# sGPSDO_MCU_1V1.net
KiCad netlist of a schematic drawn in EAGLE
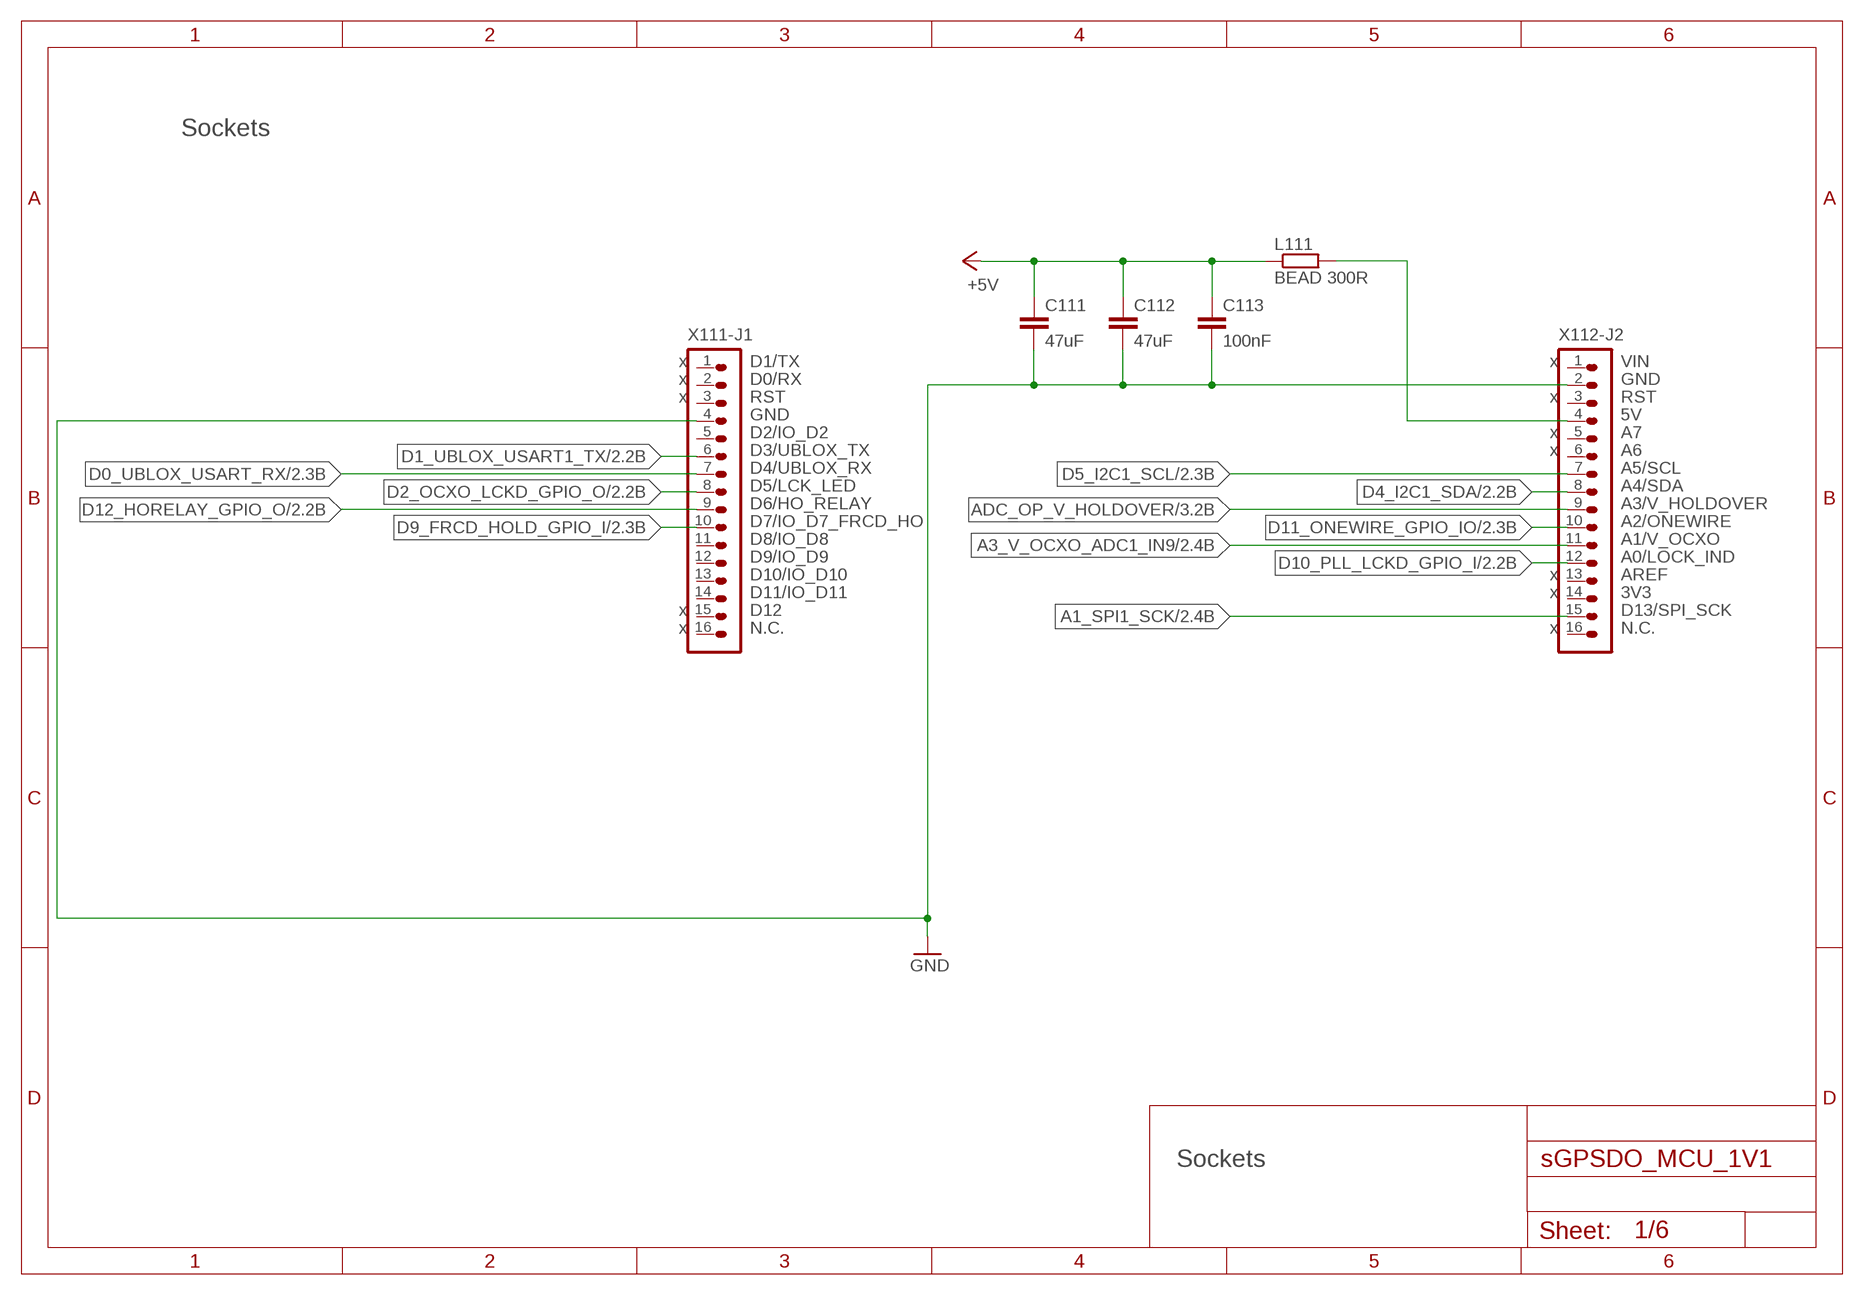
[diagram p0: schematic, sheet 1]
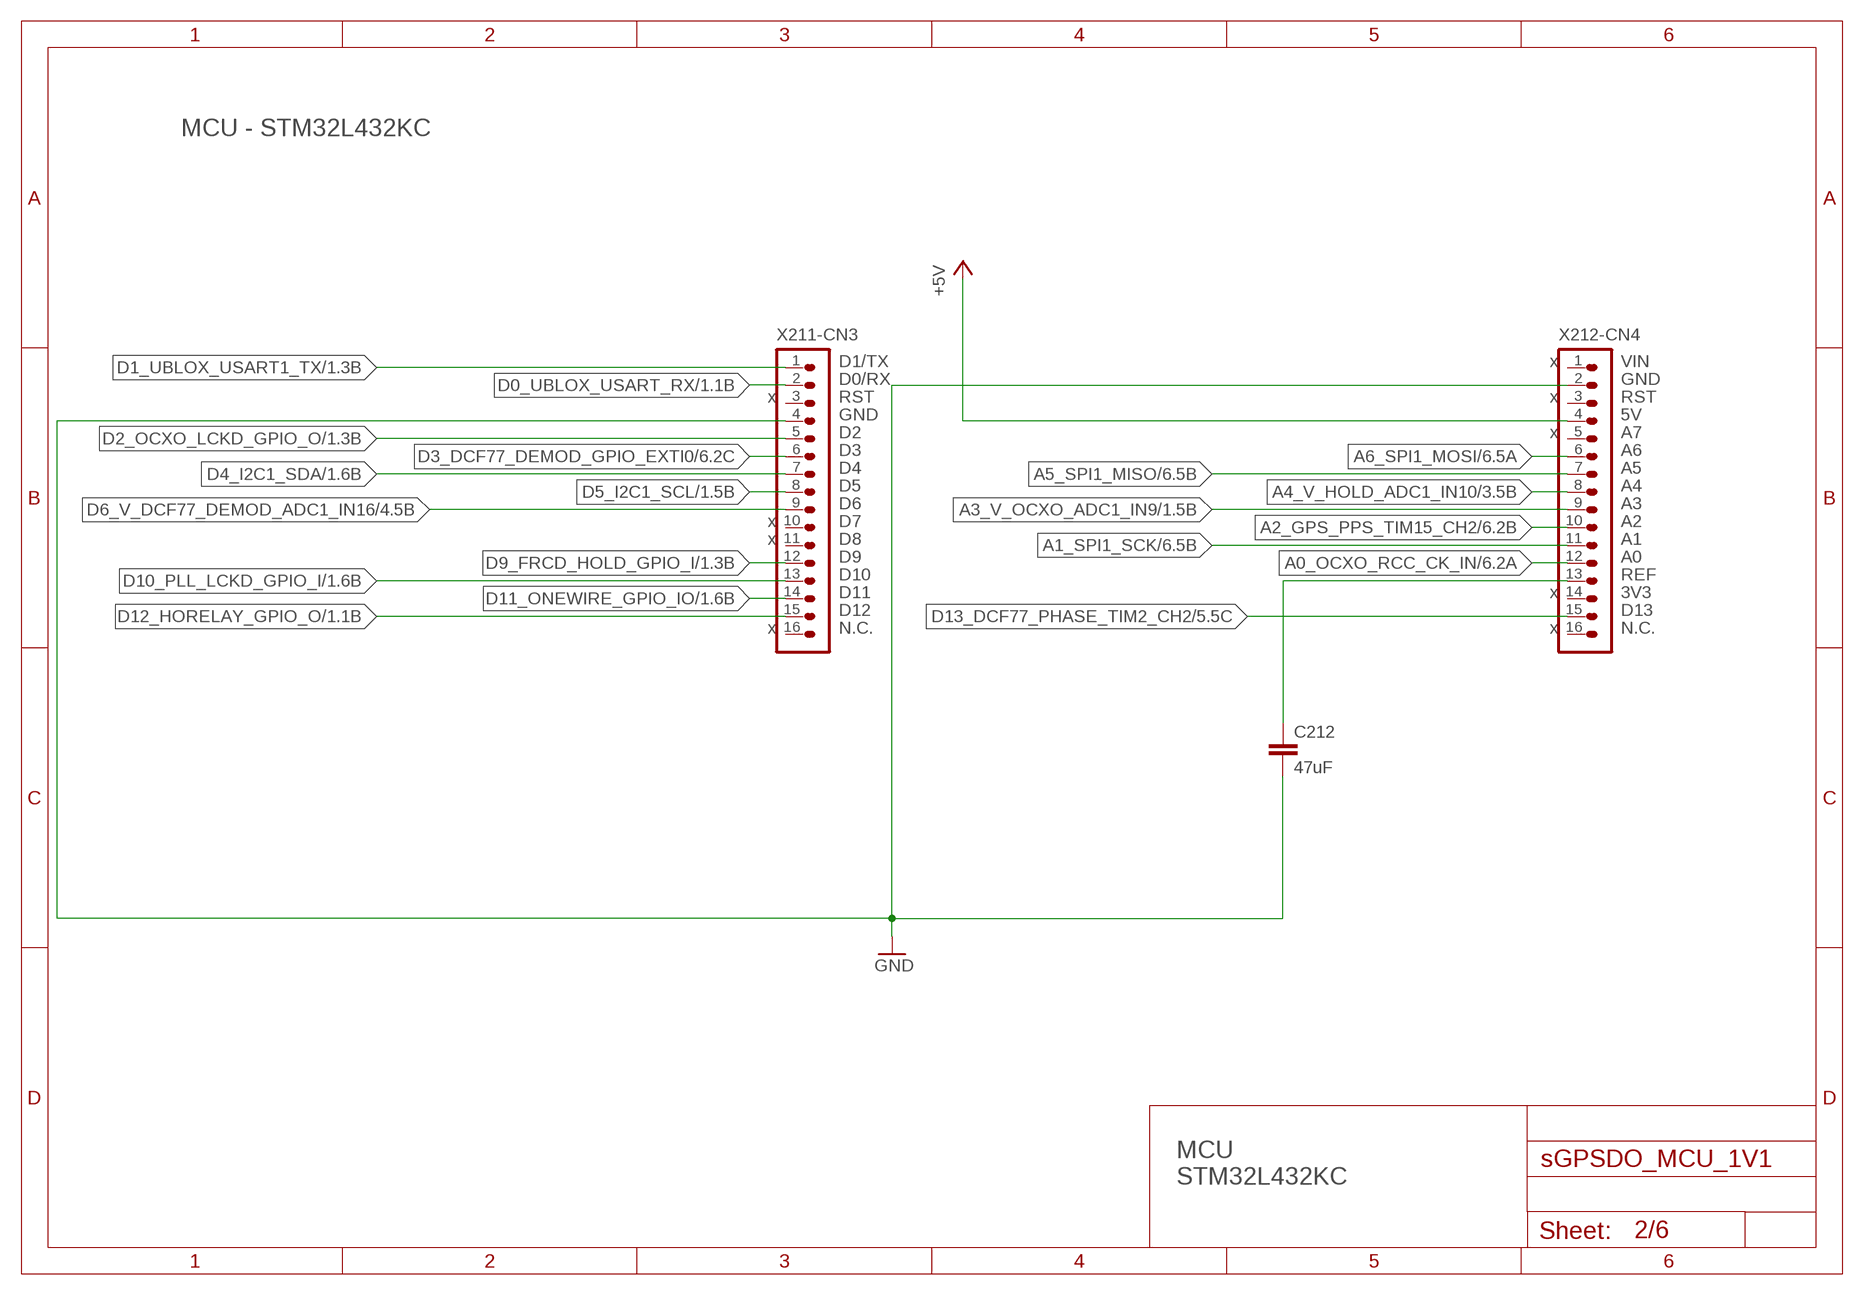
[diagram p1: schematic, sheet 2]
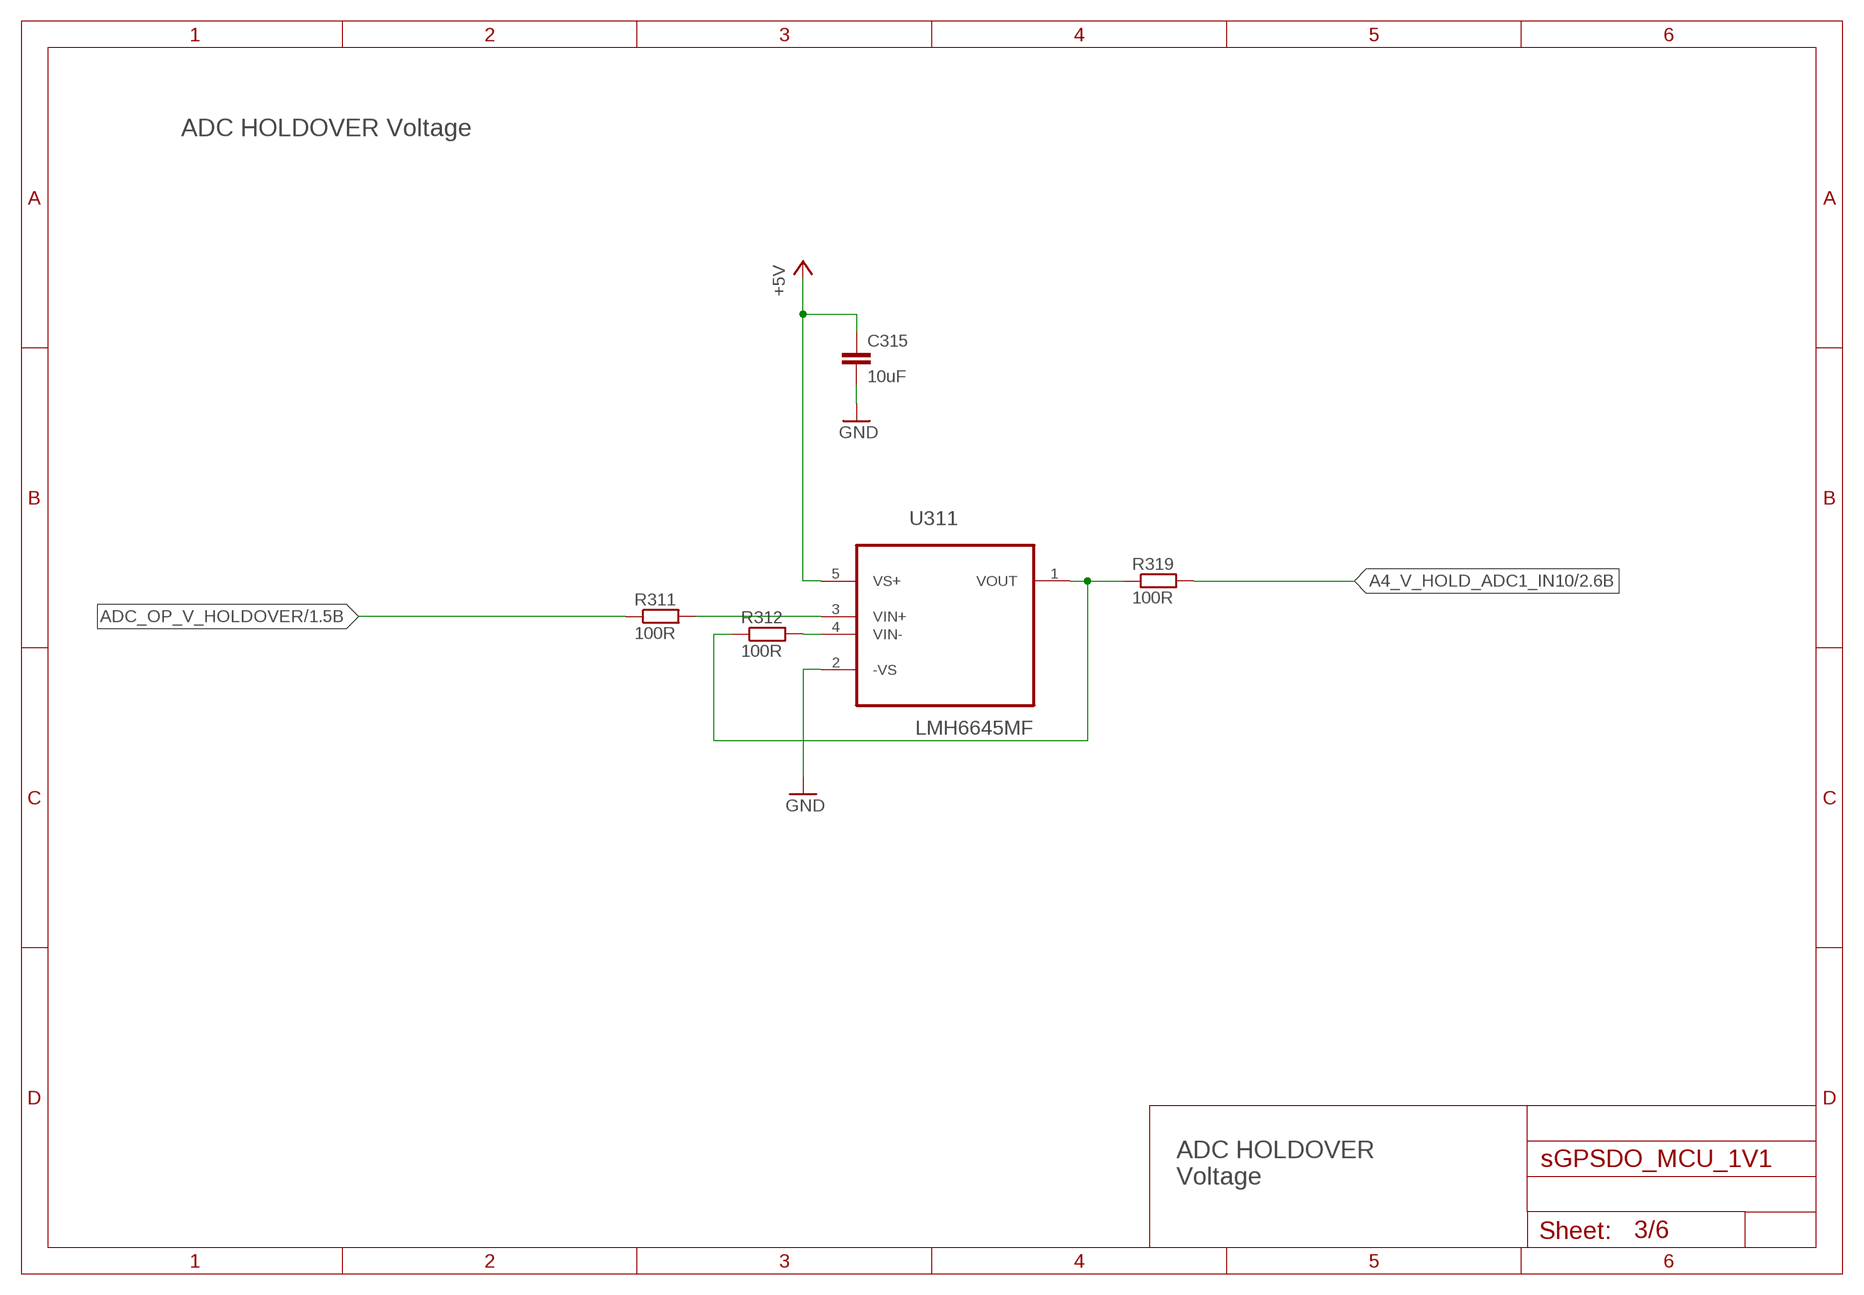
[diagram p2: schematic, sheet 3]
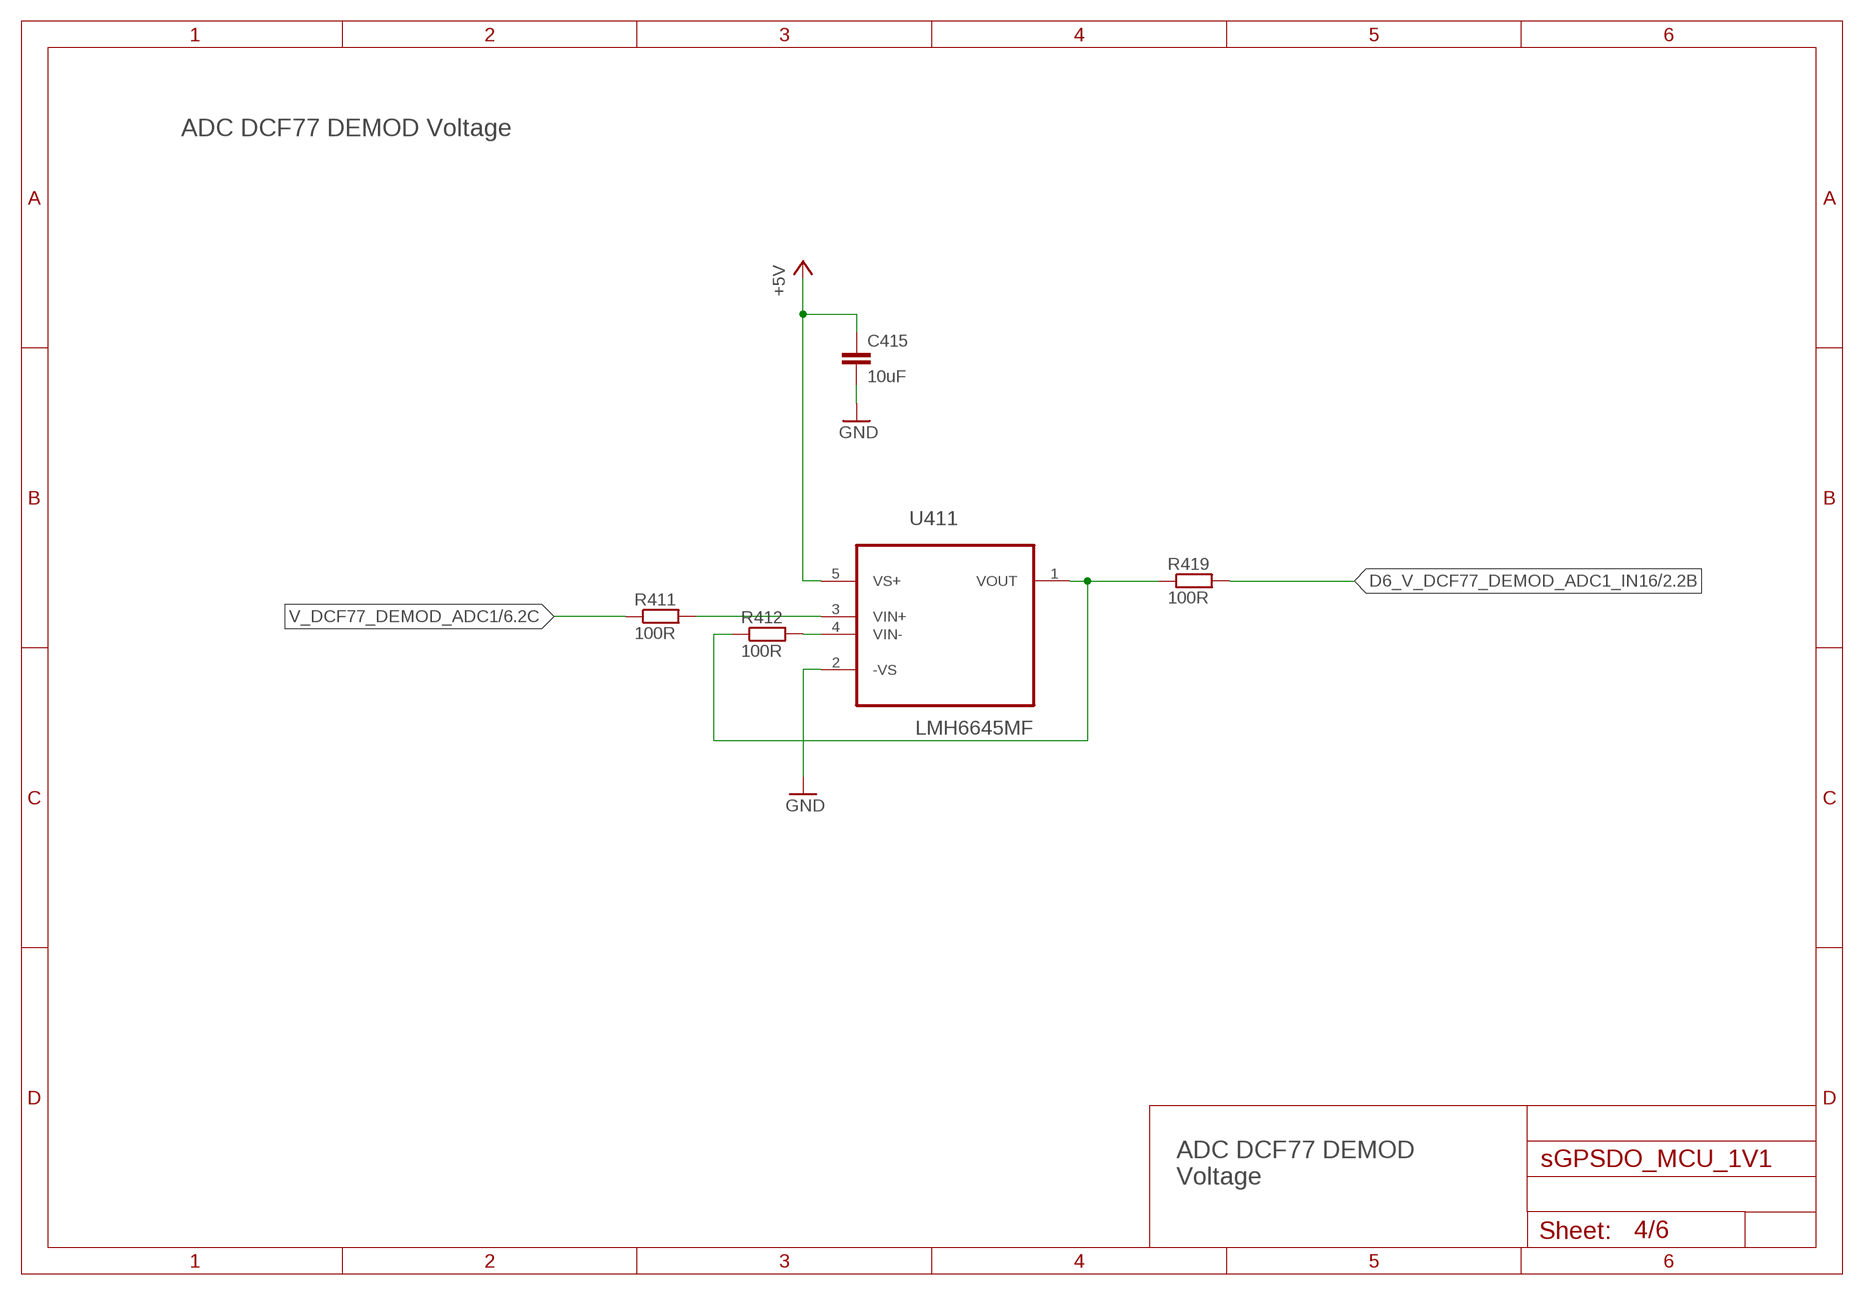
[diagram p3: schematic, sheet 4]
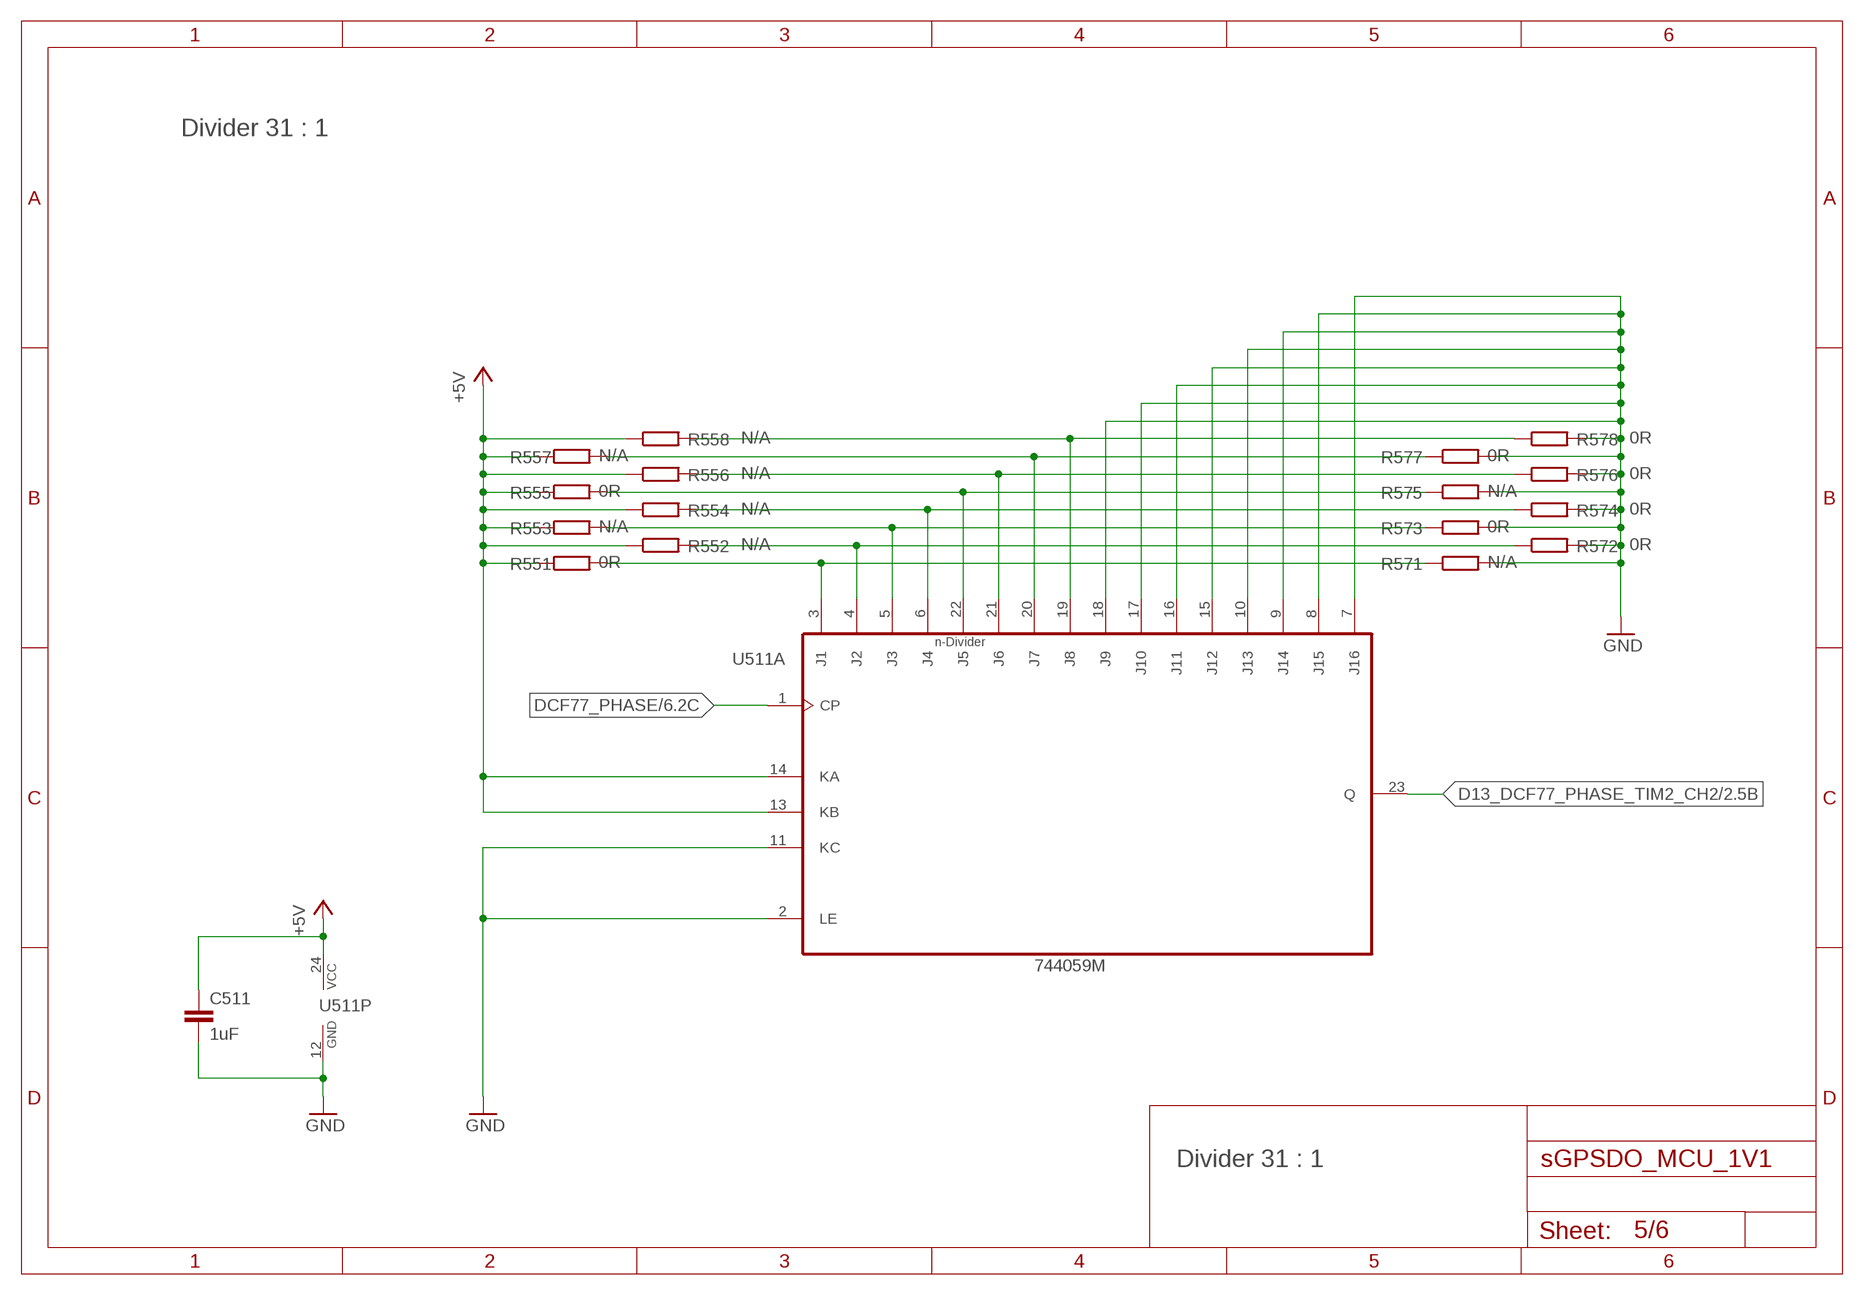
[diagram p4: schematic, sheet 5]
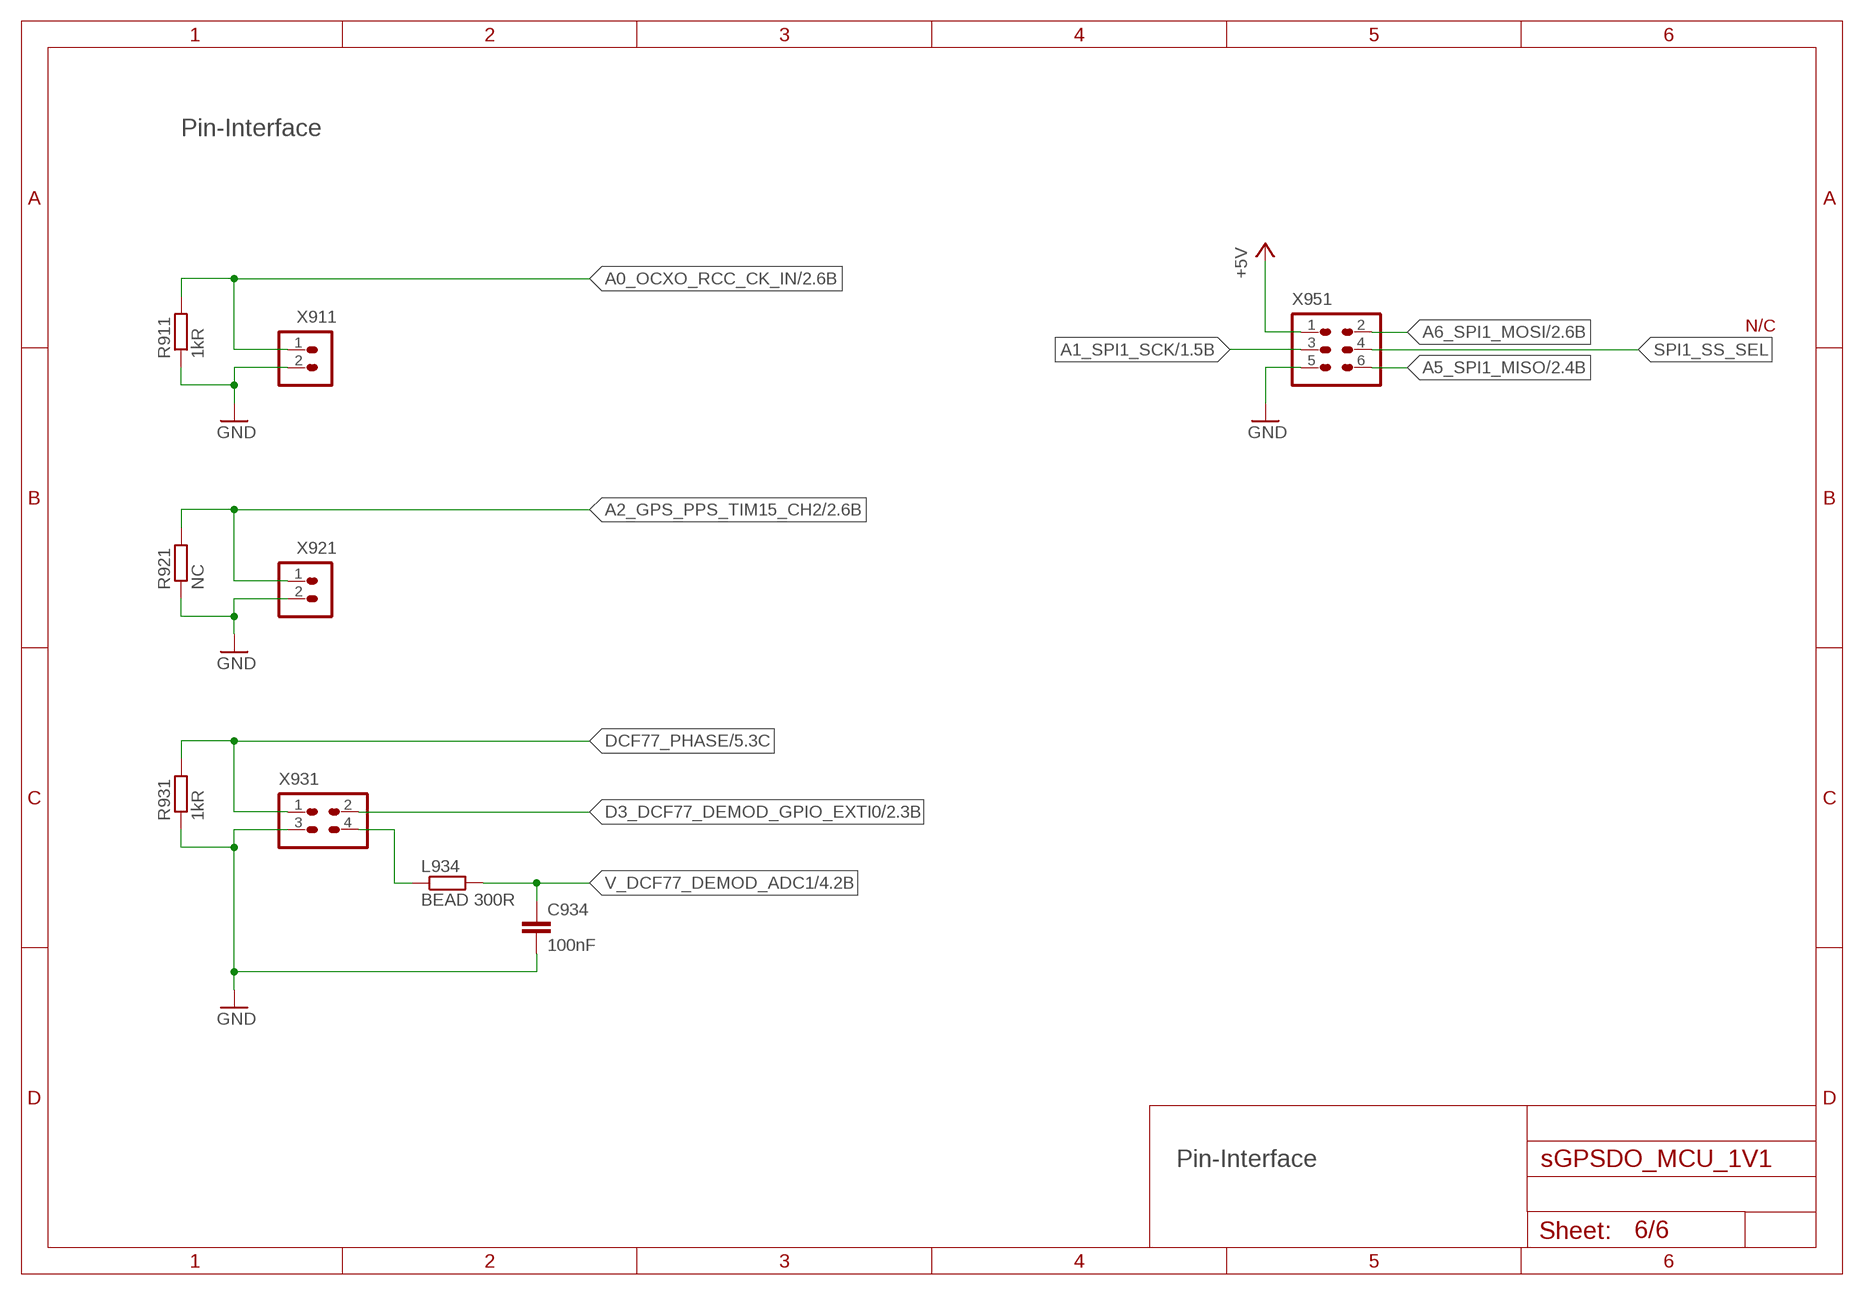
[diagram p5: schematic, sheet 6]

(export (version "E")
  (design (tool "Eeschema 10.0.6"))
  (components
    (comp (ref "C511")
      (value "1uF")
      (footprint "eagle-import:C0805")
      (libsource (lib "eagle-import") (part "C-EUC0805"))
    )
    (comp (ref "R551")
      (value "0R")
      (footprint "eagle-import:R0402")
      (libsource (lib "eagle-import") (part "R-EU_R0402"))
    )
    (comp (ref "R552")
      (value "N/A")
      (footprint "eagle-import:R0402")
      (libsource (lib "eagle-import") (part "R-EU_R0402"))
    )
    (comp (ref "R553")
      (value "N/A")
      (footprint "eagle-import:R0402")
      (libsource (lib "eagle-import") (part "R-EU_R0402"))
    )
    (comp (ref "R554")
      (value "N/A")
      (footprint "eagle-import:R0402")
      (libsource (lib "eagle-import") (part "R-EU_R0402"))
    )
    (comp (ref "R555")
      (value "0R")
      (footprint "eagle-import:R0402")
      (libsource (lib "eagle-import") (part "R-EU_R0402"))
    )
    (comp (ref "R556")
      (value "N/A")
      (footprint "eagle-import:R0402")
      (libsource (lib "eagle-import") (part "R-EU_R0402"))
    )
    (comp (ref "R557")
      (value "N/A")
      (footprint "eagle-import:R0402")
      (libsource (lib "eagle-import") (part "R-EU_R0402"))
    )
    (comp (ref "R558")
      (value "N/A")
      (footprint "eagle-import:R0402")
      (libsource (lib "eagle-import") (part "R-EU_R0402"))
    )
    (comp (ref "R571")
      (value "N/A")
      (footprint "eagle-import:R0402")
      (libsource (lib "eagle-import") (part "R-EU_R0402"))
    )
    (comp (ref "R572")
      (value "0R")
      (footprint "eagle-import:R0402")
      (libsource (lib "eagle-import") (part "R-EU_R0402"))
    )
    (comp (ref "R573")
      (value "0R")
      (footprint "eagle-import:R0402")
      (libsource (lib "eagle-import") (part "R-EU_R0402"))
    )
    (comp (ref "R574")
      (value "0R")
      (footprint "eagle-import:R0402")
      (libsource (lib "eagle-import") (part "R-EU_R0402"))
    )
    (comp (ref "R575")
      (value "N/A")
      (footprint "eagle-import:R0402")
      (libsource (lib "eagle-import") (part "R-EU_R0402"))
    )
    (comp (ref "R576")
      (value "0R")
      (footprint "eagle-import:R0402")
      (libsource (lib "eagle-import") (part "R-EU_R0402"))
    )
    (comp (ref "R577")
      (value "0R")
      (footprint "eagle-import:R0402")
      (libsource (lib "eagle-import") (part "R-EU_R0402"))
    )
    (comp (ref "R578")
      (value "0R")
      (footprint "eagle-import:R0402")
      (libsource (lib "eagle-import") (part "R-EU_R0402"))
    )
    (comp (ref "U511")
      (value "744059M")
      (footprint "eagle-import:SOIC24")
      (libsource (lib "eagle-import") (part "744059M"))
    )
    (comp (ref "C111")
      (value "47uF")
      (footprint "eagle-import:C0805")
      (libsource (lib "eagle-import") (part "C-EUC0805"))
    )
    (comp (ref "C112")
      (value "47uF")
      (footprint "eagle-import:C0805")
      (libsource (lib "eagle-import") (part "C-EUC0805"))
    )
    (comp (ref "C113")
      (value "100nF")
      (footprint "eagle-import:C0805")
      (libsource (lib "eagle-import") (part "C-EUC0805"))
    )
    (comp (ref "L111")
      (value "BEAD 300R")
      (footprint "eagle-import:R1206")
      (libsource (lib "eagle-import") (part "R-EU_R1206"))
    )
    (comp (ref "X111-J1")
      (value "HEADER-1X16")
      (footprint "eagle-import:1X16")
      (libsource (lib "eagle-import") (part "HEADER-1X16"))
    )
    (comp (ref "X112-J2")
      (value "HEADER-1X16")
      (footprint "eagle-import:1X16")
      (libsource (lib "eagle-import") (part "HEADER-1X16"))
    )
    (comp (ref "C415")
      (value "10uF")
      (footprint "eagle-import:C0805")
      (libsource (lib "eagle-import") (part "C-EUC0805"))
    )
    (comp (ref "R411")
      (value "100R")
      (footprint "eagle-import:R0805")
      (libsource (lib "eagle-import") (part "R-EU_R0805"))
    )
    (comp (ref "R412")
      (value "100R")
      (footprint "eagle-import:R0805")
      (libsource (lib "eagle-import") (part "R-EU_R0805"))
    )
    (comp (ref "R419")
      (value "100R")
      (footprint "eagle-import:R0805")
      (libsource (lib "eagle-import") (part "R-EU_R0805"))
    )
    (comp (ref "U411")
      (value "LMH6645MF")
      (footprint "eagle-import:SOT-23-5")
      (libsource (lib "eagle-import") (part "LMH6645MF"))
    )
    (comp (ref "C212")
      (value "47uF")
      (footprint "eagle-import:C0805")
      (libsource (lib "eagle-import") (part "C-EUC0805"))
    )
    (comp (ref "X211-CN3")
      (value "HEADER-1X16")
      (footprint "eagle-import:1X16")
      (libsource (lib "eagle-import") (part "HEADER-1X16"))
    )
    (comp (ref "X212-CN4")
      (value "HEADER-1X16")
      (footprint "eagle-import:1X16")
      (libsource (lib "eagle-import") (part "HEADER-1X16"))
    )
    (comp (ref "C934")
      (value "100nF")
      (footprint "eagle-import:C0805")
      (libsource (lib "eagle-import") (part "C-EUC0805"))
    )
    (comp (ref "L934")
      (value "BEAD 300R")
      (footprint "eagle-import:R1206")
      (libsource (lib "eagle-import") (part "R-EU_R1206"))
    )
    (comp (ref "R911")
      (value "1kR")
      (footprint "eagle-import:R0805")
      (libsource (lib "eagle-import") (part "R-EU_R0805"))
    )
    (comp (ref "R921")
      (value "NC")
      (footprint "eagle-import:R0805")
      (libsource (lib "eagle-import") (part "R-EU_R0805"))
    )
    (comp (ref "R931")
      (value "1kR")
      (footprint "eagle-import:R0805")
      (libsource (lib "eagle-import") (part "R-EU_R0805"))
    )
    (comp (ref "X911")
      (value "HEADER-1X2")
      (footprint "eagle-import:1X02")
      (libsource (lib "eagle-import") (part "HEADER-1X2"))
    )
    (comp (ref "X921")
      (value "HEADER-1X2")
      (footprint "eagle-import:1X02")
      (libsource (lib "eagle-import") (part "HEADER-1X2"))
    )
    (comp (ref "X931")
      (value "HEADER-2X2")
      (footprint "eagle-import:2X02")
      (libsource (lib "eagle-import") (part "HEADER-2X2"))
    )
    (comp (ref "X951")
      (value "HEADER-2X3")
      (footprint "eagle-import:2X03")
      (libsource (lib "eagle-import") (part "HEADER-2X3"))
    )
    (comp (ref "C315")
      (value "10uF")
      (footprint "eagle-import:C0805")
      (libsource (lib "eagle-import") (part "C-EUC0805"))
    )
    (comp (ref "R311")
      (value "100R")
      (footprint "eagle-import:R0805")
      (libsource (lib "eagle-import") (part "R-EU_R0805"))
    )
    (comp (ref "R312")
      (value "100R")
      (footprint "eagle-import:R0805")
      (libsource (lib "eagle-import") (part "R-EU_R0805"))
    )
    (comp (ref "R319")
      (value "100R")
      (footprint "eagle-import:R0805")
      (libsource (lib "eagle-import") (part "R-EU_R0805"))
    )
    (comp (ref "U311")
      (value "LMH6645MF")
      (footprint "eagle-import:SOT-23-5")
      (libsource (lib "eagle-import") (part "LMH6645MF"))
    )
  )
  (nets
    (net (code "1") (name "+5V") (class "Default")
      (node (ref "C111") (pin "1") (pinfunction "1_1") (pintype "passive"))
      (node (ref "C112") (pin "1") (pinfunction "1_1") (pintype "passive"))
      (node (ref "C113") (pin "1") (pinfunction "1_1") (pintype "passive"))
      (node (ref "C315") (pin "1") (pinfunction "1_1") (pintype "passive"))
      (node (ref "C415") (pin "1") (pinfunction "1_1") (pintype "passive"))
      (node (ref "C511") (pin "1") (pinfunction "1_1") (pintype "passive"))
      (node (ref "L111") (pin "1") (pinfunction "1_1") (pintype "passive"))
      (node (ref "R551") (pin "1") (pinfunction "1_1") (pintype "passive"))
      (node (ref "R552") (pin "1") (pinfunction "1_1") (pintype "passive"))
      (node (ref "R553") (pin "1") (pinfunction "1_1") (pintype "passive"))
      (node (ref "R554") (pin "1") (pinfunction "1_1") (pintype "passive"))
      (node (ref "R555") (pin "1") (pinfunction "1_1") (pintype "passive"))
      (node (ref "R556") (pin "1") (pinfunction "1_1") (pintype "passive"))
      (node (ref "R557") (pin "1") (pinfunction "1_1") (pintype "passive"))
      (node (ref "R558") (pin "1") (pinfunction "1_1") (pintype "passive"))
      (node (ref "U311") (pin "5") (pinfunction "VS+_5") (pintype "power_in"))
      (node (ref "U411") (pin "5") (pinfunction "VS+_5") (pintype "power_in"))
      (node (ref "U511") (pin "13") (pinfunction "KB_13") (pintype "input"))
      (node (ref "U511") (pin "14") (pinfunction "KA_14") (pintype "input"))
      (node (ref "U511") (pin "24") (pinfunction "VCC_24") (pintype "power_in"))
      (node (ref "X212-CN4") (pin "4") (pinfunction "4_4") (pintype "passive"))
      (node (ref "X951") (pin "1") (pinfunction "1_1") (pintype "passive"))
    )
    (net (code "2") (name "A0_OCXO_RCC_CK_IN") (class "Default")
      (node (ref "R911") (pin "2") (pinfunction "2_2") (pintype "passive"))
      (node (ref "X212-CN4") (pin "12") (pinfunction "12_12") (pintype "passive"))
      (node (ref "X911") (pin "1") (pinfunction "1_1") (pintype "passive"))
    )
    (net (code "3") (name "A1_SPI1_SCK") (class "Default")
      (node (ref "X112-J2") (pin "15") (pinfunction "15_15") (pintype "passive"))
      (node (ref "X212-CN4") (pin "11") (pinfunction "11_11") (pintype "passive"))
      (node (ref "X951") (pin "3") (pinfunction "3_3") (pintype "passive"))
    )
    (net (code "4") (name "A2_GPS_PPS_TIM15_CH2") (class "Default")
      (node (ref "R921") (pin "2") (pinfunction "2_2") (pintype "passive"))
      (node (ref "X212-CN4") (pin "10") (pinfunction "10_10") (pintype "passive"))
      (node (ref "X921") (pin "1") (pinfunction "1_1") (pintype "passive"))
    )
    (net (code "5") (name "A3_V_OCXO_ADC1_IN9") (class "Default")
      (node (ref "X112-J2") (pin "11") (pinfunction "11_11") (pintype "passive"))
      (node (ref "X212-CN4") (pin "9") (pinfunction "9_9") (pintype "passive"))
    )
    (net (code "6") (name "A4_V_HOLD_ADC1_IN10") (class "Default")
      (node (ref "R319") (pin "2") (pinfunction "2_2") (pintype "passive"))
      (node (ref "X212-CN4") (pin "8") (pinfunction "8_8") (pintype "passive"))
    )
    (net (code "7") (name "A5_SPI1_MISO") (class "Default")
      (node (ref "X212-CN4") (pin "7") (pinfunction "7_7") (pintype "passive"))
      (node (ref "X951") (pin "6") (pinfunction "6_6") (pintype "passive"))
    )
    (net (code "8") (name "A6_SPI1_MOSI") (class "Default")
      (node (ref "X212-CN4") (pin "6") (pinfunction "6_6") (pintype "passive"))
      (node (ref "X951") (pin "2") (pinfunction "2_2") (pintype "passive"))
    )
    (net (code "9") (name "ADC_OP_V_HOLDOVER") (class "Default")
      (node (ref "R311") (pin "1") (pinfunction "1_1") (pintype "passive"))
      (node (ref "X112-J2") (pin "9") (pinfunction "9_9") (pintype "passive"))
    )
    (net (code "10") (name "D0_UBLOX_USART_RX") (class "Default")
      (node (ref "X111-J1") (pin "7") (pinfunction "7_7") (pintype "passive"))
      (node (ref "X211-CN3") (pin "2") (pinfunction "2_2") (pintype "passive"))
    )
    (net (code "11") (name "D1_UBLOX_USART1_TX") (class "Default")
      (node (ref "X111-J1") (pin "6") (pinfunction "6_6") (pintype "passive"))
      (node (ref "X211-CN3") (pin "1") (pinfunction "1_1") (pintype "passive"))
    )
    (net (code "12") (name "D2_OCXO_LCKD_GPIO_O") (class "Default")
      (node (ref "X111-J1") (pin "8") (pinfunction "8_8") (pintype "passive"))
      (node (ref "X211-CN3") (pin "5") (pinfunction "5_5") (pintype "passive"))
    )
    (net (code "13") (name "D3_DCF77_DEMOD_GPIO_EXTI0") (class "Default")
      (node (ref "X211-CN3") (pin "6") (pinfunction "6_6") (pintype "passive"))
      (node (ref "X931") (pin "2") (pinfunction "2_2") (pintype "passive"))
    )
    (net (code "14") (name "D4_I2C1_SDA") (class "Default")
      (node (ref "X112-J2") (pin "8") (pinfunction "8_8") (pintype "passive"))
      (node (ref "X211-CN3") (pin "7") (pinfunction "7_7") (pintype "passive"))
    )
    (net (code "15") (name "D5_I2C1_SCL") (class "Default")
      (node (ref "X112-J2") (pin "7") (pinfunction "7_7") (pintype "passive"))
      (node (ref "X211-CN3") (pin "8") (pinfunction "8_8") (pintype "passive"))
    )
    (net (code "16") (name "D6_V_DCF77_DEMOD_ADC1_IN16") (class "Default")
      (node (ref "R419") (pin "2") (pinfunction "2_2") (pintype "passive"))
      (node (ref "X211-CN3") (pin "9") (pinfunction "9_9") (pintype "passive"))
    )
    (net (code "17") (name "D9_FRCD_HOLD_GPIO_I") (class "Default")
      (node (ref "X111-J1") (pin "10") (pinfunction "10_10") (pintype "passive"))
      (node (ref "X211-CN3") (pin "12") (pinfunction "12_12") (pintype "passive"))
    )
    (net (code "18") (name "D10_PLL_LCKD_GPIO_I") (class "Default")
      (node (ref "X112-J2") (pin "12") (pinfunction "12_12") (pintype "passive"))
      (node (ref "X211-CN3") (pin "13") (pinfunction "13_13") (pintype "passive"))
    )
    (net (code "19") (name "D11_ONEWIRE_GPIO_IO") (class "Default")
      (node (ref "X112-J2") (pin "10") (pinfunction "10_10") (pintype "passive"))
      (node (ref "X211-CN3") (pin "14") (pinfunction "14_14") (pintype "passive"))
    )
    (net (code "20") (name "D12_HORELAY_GPIO_O") (class "Default")
      (node (ref "X111-J1") (pin "9") (pinfunction "9_9") (pintype "passive"))
      (node (ref "X211-CN3") (pin "15") (pinfunction "15_15") (pintype "passive"))
    )
    (net (code "21") (name "D13_DCF77_PHASE_TIM2_CH2") (class "Default")
      (node (ref "U511") (pin "23") (pinfunction "Q_23") (pintype "output"))
      (node (ref "X212-CN4") (pin "15") (pinfunction "15_15") (pintype "passive"))
    )
    (net (code "22") (name "DCF77_PHASE") (class "Default")
      (node (ref "R931") (pin "2") (pinfunction "2_2") (pintype "passive"))
      (node (ref "U511") (pin "1") (pinfunction "CP_1") (pintype "input"))
      (node (ref "X931") (pin "1") (pinfunction "1_1") (pintype "passive"))
    )
    (net (code "23") (name "GND") (class "Default")
      (node (ref "C111") (pin "2") (pinfunction "2_2") (pintype "passive"))
      (node (ref "C112") (pin "2") (pinfunction "2_2") (pintype "passive"))
      (node (ref "C113") (pin "2") (pinfunction "2_2") (pintype "passive"))
      (node (ref "C212") (pin "2") (pinfunction "2_2") (pintype "passive"))
      (node (ref "C315") (pin "2") (pinfunction "2_2") (pintype "passive"))
      (node (ref "C415") (pin "2") (pinfunction "2_2") (pintype "passive"))
      (node (ref "C511") (pin "2") (pinfunction "2_2") (pintype "passive"))
      (node (ref "C934") (pin "2") (pinfunction "2_2") (pintype "passive"))
      (node (ref "R571") (pin "2") (pinfunction "2_2") (pintype "passive"))
      (node (ref "R572") (pin "2") (pinfunction "2_2") (pintype "passive"))
      (node (ref "R573") (pin "2") (pinfunction "2_2") (pintype "passive"))
      (node (ref "R574") (pin "2") (pinfunction "2_2") (pintype "passive"))
      (node (ref "R575") (pin "2") (pinfunction "2_2") (pintype "passive"))
      (node (ref "R576") (pin "2") (pinfunction "2_2") (pintype "passive"))
      (node (ref "R577") (pin "2") (pinfunction "2_2") (pintype "passive"))
      (node (ref "R578") (pin "2") (pinfunction "2_2") (pintype "passive"))
      (node (ref "R911") (pin "1") (pinfunction "1_1") (pintype "passive"))
      (node (ref "R921") (pin "1") (pinfunction "1_1") (pintype "passive"))
      (node (ref "R931") (pin "1") (pinfunction "1_1") (pintype "passive"))
      (node (ref "U311") (pin "2") (pinfunction "-VS_2") (pintype "power_in"))
      (node (ref "U411") (pin "2") (pinfunction "-VS_2") (pintype "power_in"))
      (node (ref "U511") (pin "10") (pinfunction "J13_10") (pintype "input"))
      (node (ref "U511") (pin "11") (pinfunction "KC_11") (pintype "input"))
      (node (ref "U511") (pin "12") (pinfunction "GND_12") (pintype "power_in"))
      (node (ref "U511") (pin "15") (pinfunction "J12_15") (pintype "input"))
      (node (ref "U511") (pin "16") (pinfunction "J11_16") (pintype "input"))
      (node (ref "U511") (pin "17") (pinfunction "J10_17") (pintype "input"))
      (node (ref "U511") (pin "18") (pinfunction "J9_18") (pintype "input"))
      (node (ref "U511") (pin "2") (pinfunction "LE_2") (pintype "input"))
      (node (ref "U511") (pin "7") (pinfunction "J16_7") (pintype "input"))
      (node (ref "U511") (pin "8") (pinfunction "J15_8") (pintype "input"))
      (node (ref "U511") (pin "9") (pinfunction "J14_9") (pintype "input"))
      (node (ref "X111-J1") (pin "4") (pinfunction "4_4") (pintype "passive"))
      (node (ref "X112-J2") (pin "2") (pinfunction "2_2") (pintype "passive"))
      (node (ref "X211-CN3") (pin "4") (pinfunction "4_4") (pintype "passive"))
      (node (ref "X212-CN4") (pin "2") (pinfunction "2_2") (pintype "passive"))
      (node (ref "X911") (pin "2") (pinfunction "2_2") (pintype "passive"))
      (node (ref "X921") (pin "2") (pinfunction "2_2") (pintype "passive"))
      (node (ref "X931") (pin "3") (pinfunction "3_3") (pintype "passive"))
      (node (ref "X951") (pin "5") (pinfunction "5_5") (pintype "passive"))
    )
    (net (code "24") (name "Net-(C212-Pad1)") (class "Default")
      (node (ref "C212") (pin "1") (pinfunction "1_1") (pintype "passive"))
      (node (ref "X212-CN4") (pin "13") (pinfunction "13_13") (pintype "passive"))
    )
    (net (code "25") (name "Net-(L111-Pad2)") (class "Default")
      (node (ref "L111") (pin "2") (pinfunction "2_2") (pintype "passive"))
      (node (ref "X112-J2") (pin "4") (pinfunction "4_4") (pintype "passive"))
    )
    (net (code "26") (name "Net-(L934-Pad1)") (class "Default")
      (node (ref "L934") (pin "1") (pinfunction "1_1") (pintype "passive"))
      (node (ref "X931") (pin "4") (pinfunction "4_4") (pintype "passive"))
    )
    (net (code "27") (name "Net-(U311-VIN+)") (class "Default")
      (node (ref "R311") (pin "2") (pinfunction "2_2") (pintype "passive"))
      (node (ref "U311") (pin "3") (pinfunction "VIN+_3") (pintype "input"))
    )
    (net (code "28") (name "Net-(U311-VIN-)") (class "Default")
      (node (ref "R312") (pin "2") (pinfunction "2_2") (pintype "passive"))
      (node (ref "U311") (pin "4") (pinfunction "VIN-_4") (pintype "input"))
    )
    (net (code "29") (name "Net-(U311-VOUT)") (class "Default")
      (node (ref "R312") (pin "1") (pinfunction "1_1") (pintype "passive"))
      (node (ref "R319") (pin "1") (pinfunction "1_1") (pintype "passive"))
      (node (ref "U311") (pin "1") (pinfunction "VOUT_1") (pintype "output"))
    )
    (net (code "30") (name "Net-(U411-VIN+)") (class "Default")
      (node (ref "R411") (pin "2") (pinfunction "2_2") (pintype "passive"))
      (node (ref "U411") (pin "3") (pinfunction "VIN+_3") (pintype "input"))
    )
    (net (code "31") (name "Net-(U411-VIN-)") (class "Default")
      (node (ref "R412") (pin "2") (pinfunction "2_2") (pintype "passive"))
      (node (ref "U411") (pin "4") (pinfunction "VIN-_4") (pintype "input"))
    )
    (net (code "32") (name "Net-(U411-VOUT)") (class "Default")
      (node (ref "R412") (pin "1") (pinfunction "1_1") (pintype "passive"))
      (node (ref "R419") (pin "1") (pinfunction "1_1") (pintype "passive"))
      (node (ref "U411") (pin "1") (pinfunction "VOUT_1") (pintype "output"))
    )
    (net (code "33") (name "Net-(U511A-J1)") (class "Default")
      (node (ref "R551") (pin "2") (pinfunction "2_2") (pintype "passive"))
      (node (ref "R571") (pin "1") (pinfunction "1_1") (pintype "passive"))
      (node (ref "U511") (pin "3") (pinfunction "J1_3") (pintype "input"))
    )
    (net (code "34") (name "Net-(U511A-J2)") (class "Default")
      (node (ref "R552") (pin "2") (pinfunction "2_2") (pintype "passive"))
      (node (ref "R572") (pin "1") (pinfunction "1_1") (pintype "passive"))
      (node (ref "U511") (pin "4") (pinfunction "J2_4") (pintype "input"))
    )
    (net (code "35") (name "Net-(U511A-J3)") (class "Default")
      (node (ref "R553") (pin "2") (pinfunction "2_2") (pintype "passive"))
      (node (ref "R573") (pin "1") (pinfunction "1_1") (pintype "passive"))
      (node (ref "U511") (pin "5") (pinfunction "J3_5") (pintype "input"))
    )
    (net (code "36") (name "Net-(U511A-J4)") (class "Default")
      (node (ref "R554") (pin "2") (pinfunction "2_2") (pintype "passive"))
      (node (ref "R574") (pin "1") (pinfunction "1_1") (pintype "passive"))
      (node (ref "U511") (pin "6") (pinfunction "J4_6") (pintype "input"))
    )
    (net (code "37") (name "Net-(U511A-J5)") (class "Default")
      (node (ref "R555") (pin "2") (pinfunction "2_2") (pintype "passive"))
      (node (ref "R575") (pin "1") (pinfunction "1_1") (pintype "passive"))
      (node (ref "U511") (pin "22") (pinfunction "J5_22") (pintype "input"))
    )
    (net (code "38") (name "Net-(U511A-J6)") (class "Default")
      (node (ref "R556") (pin "2") (pinfunction "2_2") (pintype "passive"))
      (node (ref "R576") (pin "1") (pinfunction "1_1") (pintype "passive"))
      (node (ref "U511") (pin "21") (pinfunction "J6_21") (pintype "input"))
    )
    (net (code "39") (name "Net-(U511A-J7)") (class "Default")
      (node (ref "R557") (pin "2") (pinfunction "2_2") (pintype "passive"))
      (node (ref "R577") (pin "1") (pinfunction "1_1") (pintype "passive"))
      (node (ref "U511") (pin "20") (pinfunction "J7_20") (pintype "input"))
    )
    (net (code "40") (name "Net-(U511A-J8)") (class "Default")
      (node (ref "R558") (pin "2") (pinfunction "2_2") (pintype "passive"))
      (node (ref "R578") (pin "1") (pinfunction "1_1") (pintype "passive"))
      (node (ref "U511") (pin "19") (pinfunction "J8_19") (pintype "input"))
    )
    (net (code "41") (name "SPI1_SS_SEL") (class "Default")
      (node (ref "X951") (pin "4") (pinfunction "4_4") (pintype "passive"))
    )
    (net (code "42") (name "V_DCF77_DEMOD_ADC1") (class "Default")
      (node (ref "C934") (pin "1") (pinfunction "1_1") (pintype "passive"))
      (node (ref "L934") (pin "2") (pinfunction "2_2") (pintype "passive"))
      (node (ref "R411") (pin "1") (pinfunction "1_1") (pintype "passive"))
    )
    (net (code "43") (name "unconnected-(X111-J1-Pad1)") (class "Default")
      (node (ref "X111-J1") (pin "1") (pinfunction "1_1") (pintype "passive"))
    )
    (net (code "44") (name "unconnected-(X111-J1-Pad2)") (class "Default")
      (node (ref "X111-J1") (pin "2") (pinfunction "2_2") (pintype "passive"))
    )
    (net (code "45") (name "unconnected-(X111-J1-Pad3)") (class "Default")
      (node (ref "X111-J1") (pin "3") (pinfunction "3_3") (pintype "passive"))
    )
    (net (code "46") (name "unconnected-(X111-J1-Pad5)") (class "Default")
      (node (ref "X111-J1") (pin "5") (pinfunction "5_5") (pintype "passive"))
    )
    (net (code "47") (name "unconnected-(X111-J1-Pad11)") (class "Default")
      (node (ref "X111-J1") (pin "11") (pinfunction "11_11") (pintype "passive"))
    )
    (net (code "48") (name "unconnected-(X111-J1-Pad12)") (class "Default")
      (node (ref "X111-J1") (pin "12") (pinfunction "12_12") (pintype "passive"))
    )
    (net (code "49") (name "unconnected-(X111-J1-Pad13)") (class "Default")
      (node (ref "X111-J1") (pin "13") (pinfunction "13_13") (pintype "passive"))
    )
    (net (code "50") (name "unconnected-(X111-J1-Pad14)") (class "Default")
      (node (ref "X111-J1") (pin "14") (pinfunction "14_14") (pintype "passive"))
    )
    (net (code "51") (name "unconnected-(X111-J1-Pad15)") (class "Default")
      (node (ref "X111-J1") (pin "15") (pinfunction "15_15") (pintype "passive"))
    )
    (net (code "52") (name "unconnected-(X111-J1-Pad16)") (class "Default")
      (node (ref "X111-J1") (pin "16") (pinfunction "16_16") (pintype "passive"))
    )
    (net (code "53") (name "unconnected-(X112-J2-Pad1)") (class "Default")
      (node (ref "X112-J2") (pin "1") (pinfunction "1_1") (pintype "passive"))
    )
    (net (code "54") (name "unconnected-(X112-J2-Pad3)") (class "Default")
      (node (ref "X112-J2") (pin "3") (pinfunction "3_3") (pintype "passive"))
    )
    (net (code "55") (name "unconnected-(X112-J2-Pad5)") (class "Default")
      (node (ref "X112-J2") (pin "5") (pinfunction "5_5") (pintype "passive"))
    )
    (net (code "56") (name "unconnected-(X112-J2-Pad6)") (class "Default")
      (node (ref "X112-J2") (pin "6") (pinfunction "6_6") (pintype "passive"))
    )
    (net (code "57") (name "unconnected-(X112-J2-Pad13)") (class "Default")
      (node (ref "X112-J2") (pin "13") (pinfunction "13_13") (pintype "passive"))
    )
    (net (code "58") (name "unconnected-(X112-J2-Pad14)") (class "Default")
      (node (ref "X112-J2") (pin "14") (pinfunction "14_14") (pintype "passive"))
    )
    (net (code "59") (name "unconnected-(X112-J2-Pad16)") (class "Default")
      (node (ref "X112-J2") (pin "16") (pinfunction "16_16") (pintype "passive"))
    )
    (net (code "60") (name "unconnected-(X211-CN3-Pad3)") (class "Default")
      (node (ref "X211-CN3") (pin "3") (pinfunction "3_3") (pintype "passive"))
    )
    (net (code "61") (name "unconnected-(X211-CN3-Pad10)") (class "Default")
      (node (ref "X211-CN3") (pin "10") (pinfunction "10_10") (pintype "passive"))
    )
    (net (code "62") (name "unconnected-(X211-CN3-Pad11)") (class "Default")
      (node (ref "X211-CN3") (pin "11") (pinfunction "11_11") (pintype "passive"))
    )
    (net (code "63") (name "unconnected-(X211-CN3-Pad16)") (class "Default")
      (node (ref "X211-CN3") (pin "16") (pinfunction "16_16") (pintype "passive"))
    )
    (net (code "64") (name "unconnected-(X212-CN4-Pad1)") (class "Default")
      (node (ref "X212-CN4") (pin "1") (pinfunction "1_1") (pintype "passive"))
    )
    (net (code "65") (name "unconnected-(X212-CN4-Pad3)") (class "Default")
      (node (ref "X212-CN4") (pin "3") (pinfunction "3_3") (pintype "passive"))
    )
    (net (code "66") (name "unconnected-(X212-CN4-Pad5)") (class "Default")
      (node (ref "X212-CN4") (pin "5") (pinfunction "5_5") (pintype "passive"))
    )
    (net (code "67") (name "unconnected-(X212-CN4-Pad14)") (class "Default")
      (node (ref "X212-CN4") (pin "14") (pinfunction "14_14") (pintype "passive"))
    )
    (net (code "68") (name "unconnected-(X212-CN4-Pad16)") (class "Default")
      (node (ref "X212-CN4") (pin "16") (pinfunction "16_16") (pintype "passive"))
    )
  )
)
